# current_sensor.net
KiCad netlist of a schematic drawn in Altium Designer
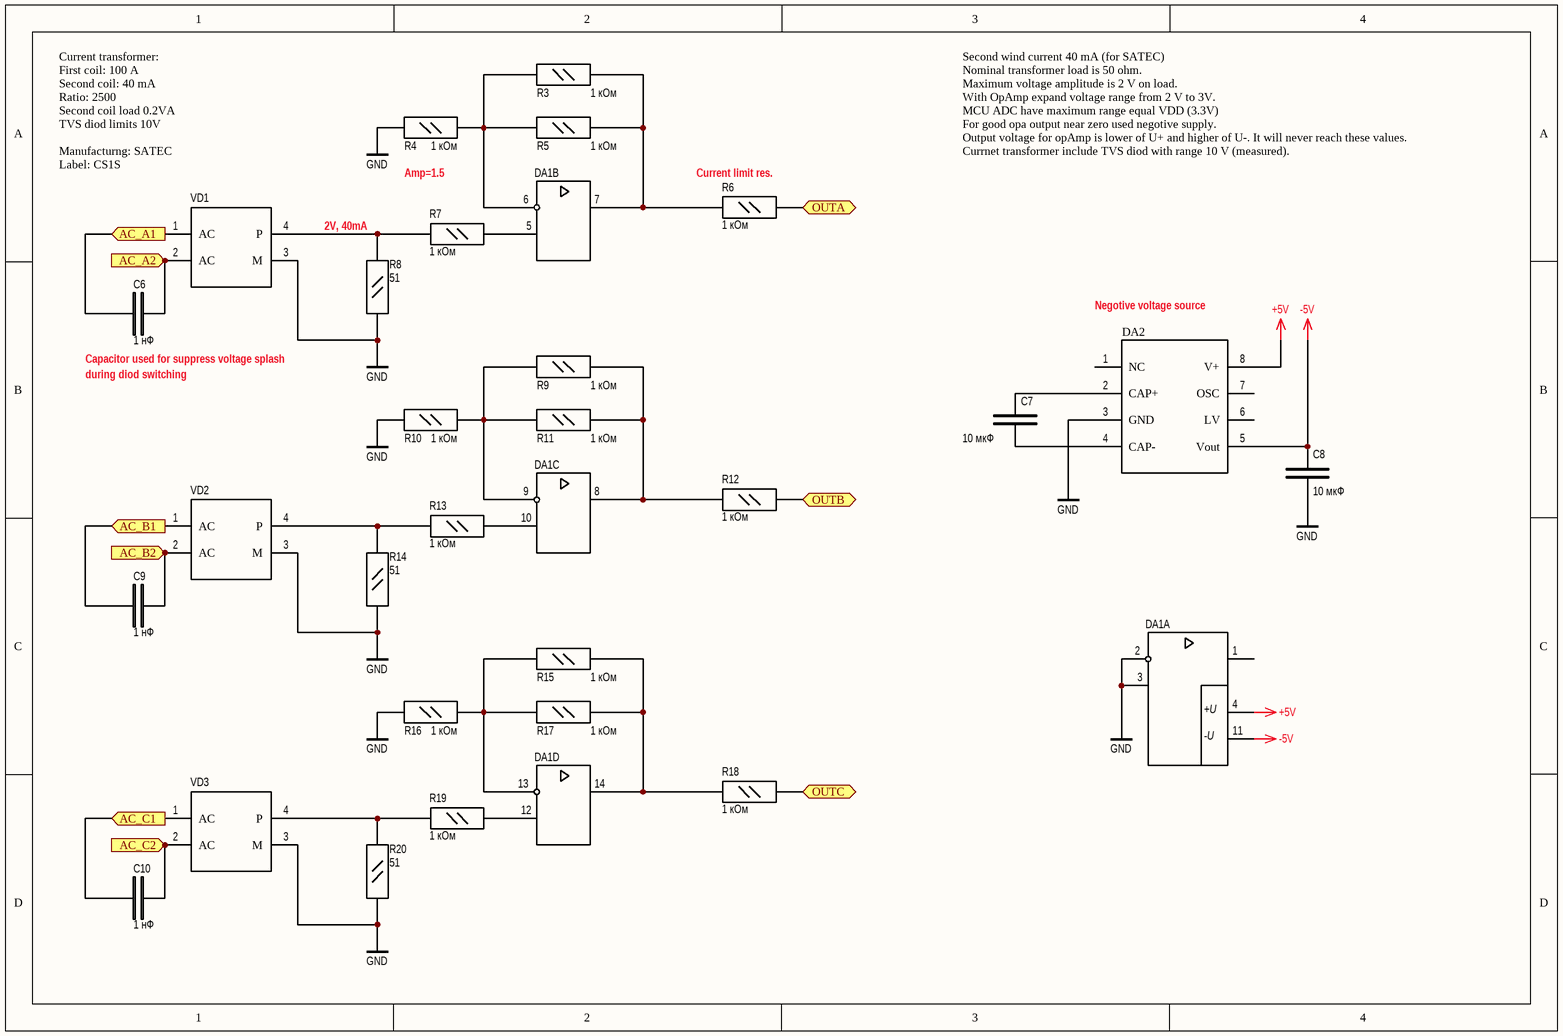
[diagram p0: current_sensor.SchDoc]

(export (version "E")
  (design (tool "Eeschema 10.0.6"))
  (components
    (comp (ref "C6")
      (value "1 нФ")
      (footprint "CAP0402-LONG")
      (description "Конденсатор")
      (libsource (lib "Passive") (part "CAP0805"))
    )
    (comp (ref "C7")
      (value "10 мкФ")
      (footprint "CAP0805")
      (description "Конденсатор")
      (libsource (lib "") (part "CAP0805_1"))
    )
    (comp (ref "C8")
      (value "10 мкФ")
      (footprint "CAP0805")
      (description "Конденсатор")
      (libsource (lib "") (part "CAP0805_1"))
    )
    (comp (ref "C9")
      (value "1 нФ")
      (footprint "CAP0402-LONG")
      (description "Конденсатор")
      (libsource (lib "Passive") (part "CAP0805"))
    )
    (comp (ref "C10")
      (value "1 нФ")
      (footprint "CAP0402-LONG")
      (description "Конденсатор")
      (libsource (lib "Passive") (part "CAP0805"))
    )
    (comp (ref "DA1")
      (value "?")
      (footprint "SO-14")
      (description "Low Power Quad Operational Amplifiers")
      (fields (field (name "PARTNUMBER") "LM324AD,LM324A,LM324DR2G"))
      (libsource (lib "IC") (part "LM324"))
    )
    (comp (ref "DA2")
      (value "ICL7660A")
      (footprint "So-8")
      (fields (field (name "PARTNUMBER") "ICL7660A,ICL7660AIBAZA-T"))
      (libsource (lib "IC") (part "ICL7660A"))
    )
    (comp (ref "R3")
      (value "1 кОм")
      (footprint "RES0402-LONG")
      (description "Резистор 0805")
      (fields (field (name "Comment") "RES0805"))
      (libsource (lib "Passive") (part "RES0805"))
    )
    (comp (ref "R4")
      (value "1 кОм")
      (footprint "RES0402-LONG")
      (description "Резистор 0805")
      (fields (field (name "Comment") "RES0805"))
      (libsource (lib "Passive") (part "RES0805"))
    )
    (comp (ref "R5")
      (value "1 кОм")
      (footprint "RES0402-LONG")
      (description "Резистор 0805")
      (fields (field (name "Comment") "RES0805"))
      (libsource (lib "Passive") (part "RES0805"))
    )
    (comp (ref "R6")
      (value "1 кОм")
      (footprint "RES0402-LONG")
      (description "Резистор 0805")
      (fields (field (name "Comment") "RES0805"))
      (libsource (lib "Passive") (part "RES0805"))
    )
    (comp (ref "R7")
      (value "1 кОм")
      (footprint "RES0402-LONG")
      (description "Резистор 0805")
      (fields (field (name "Comment") "RES0805"))
      (libsource (lib "Passive") (part "RES0805"))
    )
    (comp (ref "R8")
      (value "51")
      (footprint "RES0805")
      (fields (field (name "Comment") "Резистор 0.125Вт"))
      (libsource (lib "Passive") (part "Резистор 0.125Вт"))
    )
    (comp (ref "R9")
      (value "1 кОм")
      (footprint "RES0402-LONG")
      (description "Резистор 0805")
      (fields (field (name "Comment") "RES0805"))
      (libsource (lib "Passive") (part "RES0805"))
    )
    (comp (ref "R10")
      (value "1 кОм")
      (footprint "RES0402-LONG")
      (description "Резистор 0805")
      (fields (field (name "Comment") "RES0805"))
      (libsource (lib "Passive") (part "RES0805"))
    )
    (comp (ref "R11")
      (value "1 кОм")
      (footprint "RES0402-LONG")
      (description "Резистор 0805")
      (fields (field (name "Comment") "RES0805"))
      (libsource (lib "Passive") (part "RES0805"))
    )
    (comp (ref "R12")
      (value "1 кОм")
      (footprint "RES0402-LONG")
      (description "Резистор 0805")
      (fields (field (name "Comment") "RES0805"))
      (libsource (lib "Passive") (part "RES0805"))
    )
    (comp (ref "R13")
      (value "1 кОм")
      (footprint "RES0402-LONG")
      (description "Резистор 0805")
      (fields (field (name "Comment") "RES0805"))
      (libsource (lib "Passive") (part "RES0805"))
    )
    (comp (ref "R14")
      (value "51")
      (footprint "RES0805")
      (fields (field (name "Comment") "Резистор 0.125Вт"))
      (libsource (lib "Passive") (part "Резистор 0.125Вт"))
    )
    (comp (ref "R15")
      (value "1 кОм")
      (footprint "RES0402-LONG")
      (description "Резистор 0805")
      (fields (field (name "Comment") "RES0805"))
      (libsource (lib "Passive") (part "RES0805"))
    )
    (comp (ref "R16")
      (value "1 кОм")
      (footprint "RES0402-LONG")
      (description "Резистор 0805")
      (fields (field (name "Comment") "RES0805"))
      (libsource (lib "Passive") (part "RES0805"))
    )
    (comp (ref "R17")
      (value "1 кОм")
      (footprint "RES0402-LONG")
      (description "Резистор 0805")
      (fields (field (name "Comment") "RES0805"))
      (libsource (lib "Passive") (part "RES0805"))
    )
    (comp (ref "R18")
      (value "1 кОм")
      (footprint "RES0402-LONG")
      (description "Резистор 0805")
      (fields (field (name "Comment") "RES0805"))
      (libsource (lib "Passive") (part "RES0805"))
    )
    (comp (ref "R19")
      (value "1 кОм")
      (footprint "RES0402-LONG")
      (description "Резистор 0805")
      (fields (field (name "Comment") "RES0805"))
      (libsource (lib "Passive") (part "RES0805"))
    )
    (comp (ref "R20")
      (value "51")
      (footprint "RES0805")
      (fields (field (name "Comment") "Резистор 0.125Вт"))
      (libsource (lib "Passive") (part "Резистор 0.125Вт"))
    )
    (comp (ref "VD1") (value "DB-1MS") (footprint "DB1MA") (libsource (lib "Semiconductor") (part "DB-1MS")))
    (comp (ref "VD2") (value "DB-1MS") (footprint "DB1MA") (libsource (lib "Semiconductor") (part "DB-1MS")))
    (comp (ref "VD3") (value "DB-1MS") (footprint "DB1MA") (libsource (lib "Semiconductor") (part "DB-1MS")))
  )
  (nets
    (net (code "1") (name "+5V") (class "Default")
      (node (ref "DA1") (pin "4") (pinfunction "U+_4") (pintype "power_in"))
      (node (ref "DA2") (pin "8") (pinfunction "V+_8") (pintype "passive"))
    )
    (net (code "2") (name "-5V") (class "Default")
      (node (ref "C8") (pin "2") (pinfunction "2_2") (pintype "passive"))
      (node (ref "DA1") (pin "11") (pinfunction "U-_11") (pintype "power_in"))
      (node (ref "DA2") (pin "5") (pinfunction "Vout_5") (pintype "passive"))
    )
    (net (code "3") (name "/AC_A1") (class "Default")
      (node (ref "C6") (pin "1") (pinfunction "1_1") (pintype "passive"))
      (node (ref "VD1") (pin "1") (pinfunction "AC_1") (pintype "passive"))
    )
    (net (code "4") (name "/AC_A2") (class "Default")
      (node (ref "C6") (pin "2") (pinfunction "2_2") (pintype "passive"))
      (node (ref "VD1") (pin "2") (pinfunction "AC_2") (pintype "passive"))
    )
    (net (code "5") (name "/AC_B1") (class "Default")
      (node (ref "C9") (pin "1") (pinfunction "1_1") (pintype "passive"))
      (node (ref "VD2") (pin "1") (pinfunction "AC_1") (pintype "passive"))
    )
    (net (code "6") (name "/AC_B2") (class "Default")
      (node (ref "C9") (pin "2") (pinfunction "2_2") (pintype "passive"))
      (node (ref "VD2") (pin "2") (pinfunction "AC_2") (pintype "passive"))
    )
    (net (code "7") (name "/AC_C1") (class "Default")
      (node (ref "C10") (pin "1") (pinfunction "1_1") (pintype "passive"))
      (node (ref "VD3") (pin "1") (pinfunction "AC_1") (pintype "passive"))
    )
    (net (code "8") (name "/AC_C2") (class "Default")
      (node (ref "C10") (pin "2") (pinfunction "2_2") (pintype "passive"))
      (node (ref "VD3") (pin "2") (pinfunction "AC_2") (pintype "passive"))
    )
    (net (code "9") (name "/OUTA") (class "Default") (node (ref "R6") (pin "1") (pintype "passive")))
    (net (code "10") (name "/OUTB") (class "Default") (node (ref "R12") (pin "1") (pintype "passive")))
    (net (code "11") (name "/OUTC") (class "Default") (node (ref "R18") (pin "1") (pintype "passive")))
    (net (code "12") (name "GND") (class "Default")
      (node (ref "C8") (pin "1") (pinfunction "1_1") (pintype "passive"))
      (node (ref "DA1") (pin "2") (pinfunction "IN1-_2") (pintype "passive"))
      (node (ref "DA1") (pin "3") (pinfunction "IN1+_3") (pintype "passive"))
      (node (ref "DA2") (pin "3") (pinfunction "GND_3") (pintype "passive"))
      (node (ref "R10") (pin "2") (pintype "passive"))
      (node (ref "R14") (pin "1") (pintype "passive"))
      (node (ref "R16") (pin "2") (pintype "passive"))
      (node (ref "R20") (pin "1") (pintype "passive"))
      (node (ref "R4") (pin "2") (pintype "passive"))
      (node (ref "R8") (pin "1") (pintype "passive"))
      (node (ref "VD1") (pin "3") (pinfunction "M_3") (pintype "passive"))
      (node (ref "VD2") (pin "3") (pinfunction "M_3") (pintype "passive"))
      (node (ref "VD3") (pin "3") (pinfunction "M_3") (pintype "passive"))
    )
    (net (code "13") (name "Net-(DA1B-IN2+)") (class "Default")
      (node (ref "DA1") (pin "5") (pinfunction "IN2+_5") (pintype "passive"))
      (node (ref "R7") (pin "1") (pintype "passive"))
    )
    (net (code "14") (name "Net-(DA1B-IN2-)") (class "Default")
      (node (ref "DA1") (pin "6") (pinfunction "IN2-_6") (pintype "passive"))
      (node (ref "R3") (pin "2") (pintype "passive"))
      (node (ref "R4") (pin "1") (pintype "passive"))
      (node (ref "R5") (pin "2") (pintype "passive"))
    )
    (net (code "15") (name "Net-(DA1B-OUT2)") (class "Default")
      (node (ref "DA1") (pin "7") (pinfunction "OUT2_7") (pintype "passive"))
      (node (ref "R3") (pin "1") (pintype "passive"))
      (node (ref "R5") (pin "1") (pintype "passive"))
      (node (ref "R6") (pin "2") (pintype "passive"))
    )
    (net (code "16") (name "Net-(DA1C-IN3+)") (class "Default")
      (node (ref "DA1") (pin "10") (pinfunction "IN3+_10") (pintype "passive"))
      (node (ref "R13") (pin "1") (pintype "passive"))
    )
    (net (code "17") (name "Net-(DA1C-IN3-)") (class "Default")
      (node (ref "DA1") (pin "9") (pinfunction "IN3-_9") (pintype "passive"))
      (node (ref "R10") (pin "1") (pintype "passive"))
      (node (ref "R11") (pin "2") (pintype "passive"))
      (node (ref "R9") (pin "2") (pintype "passive"))
    )
    (net (code "18") (name "Net-(DA1C-OUT3)") (class "Default")
      (node (ref "DA1") (pin "8") (pinfunction "OUT3_8") (pintype "passive"))
      (node (ref "R11") (pin "1") (pintype "passive"))
      (node (ref "R12") (pin "2") (pintype "passive"))
      (node (ref "R9") (pin "1") (pintype "passive"))
    )
    (net (code "19") (name "Net-(DA1D-IN4+)") (class "Default")
      (node (ref "DA1") (pin "12") (pinfunction "IN4+_12") (pintype "passive"))
      (node (ref "R19") (pin "1") (pintype "passive"))
    )
    (net (code "20") (name "Net-(DA1D-IN4-)") (class "Default")
      (node (ref "DA1") (pin "13") (pinfunction "IN4-_13") (pintype "passive"))
      (node (ref "R15") (pin "2") (pintype "passive"))
      (node (ref "R16") (pin "1") (pintype "passive"))
      (node (ref "R17") (pin "2") (pintype "passive"))
    )
    (net (code "21") (name "Net-(DA1D-OUT4)") (class "Default")
      (node (ref "DA1") (pin "14") (pinfunction "OUT4_14") (pintype "passive"))
      (node (ref "R15") (pin "1") (pintype "passive"))
      (node (ref "R17") (pin "1") (pintype "passive"))
      (node (ref "R18") (pin "2") (pintype "passive"))
    )
    (net (code "22") (name "Net-(DA2-CAP+)") (class "Default")
      (node (ref "C7") (pin "2") (pinfunction "2_2") (pintype "passive"))
      (node (ref "DA2") (pin "2") (pinfunction "CAP+_2") (pintype "passive"))
    )
    (net (code "23") (name "Net-(DA2-CAP-)") (class "Default")
      (node (ref "C7") (pin "1") (pinfunction "1_1") (pintype "passive"))
      (node (ref "DA2") (pin "4") (pinfunction "CAP-_4") (pintype "passive"))
    )
    (net (code "24") (name "Net-(VD1-P)") (class "Default")
      (node (ref "R7") (pin "2") (pintype "passive"))
      (node (ref "R8") (pin "2") (pintype "passive"))
      (node (ref "VD1") (pin "4") (pinfunction "P_4") (pintype "passive"))
    )
    (net (code "25") (name "Net-(VD2-P)") (class "Default")
      (node (ref "R13") (pin "2") (pintype "passive"))
      (node (ref "R14") (pin "2") (pintype "passive"))
      (node (ref "VD2") (pin "4") (pinfunction "P_4") (pintype "passive"))
    )
    (net (code "26") (name "Net-(VD3-P)") (class "Default")
      (node (ref "R19") (pin "2") (pintype "passive"))
      (node (ref "R20") (pin "2") (pintype "passive"))
      (node (ref "VD3") (pin "4") (pinfunction "P_4") (pintype "passive"))
    )
    (net (code "27") (name "unconnected-(DA1A-OUT1-Pad1)") (class "Default")
      (node (ref "DA1") (pin "1") (pinfunction "OUT1_1") (pintype "passive"))
    )
    (net (code "28") (name "unconnected-(DA2-LV-Pad6)") (class "Default")
      (node (ref "DA2") (pin "6") (pinfunction "LV_6") (pintype "passive"))
    )
    (net (code "29") (name "unconnected-(DA2-NC-Pad1)") (class "Default")
      (node (ref "DA2") (pin "1") (pinfunction "NC_1") (pintype "passive"))
    )
    (net (code "30") (name "unconnected-(DA2-OSC-Pad7)") (class "Default")
      (node (ref "DA2") (pin "7") (pinfunction "OSC_7") (pintype "passive"))
    )
  )
)
